# MaquetaConejos_2.net
KiCad netlist of a schematic drawn in EAGLE
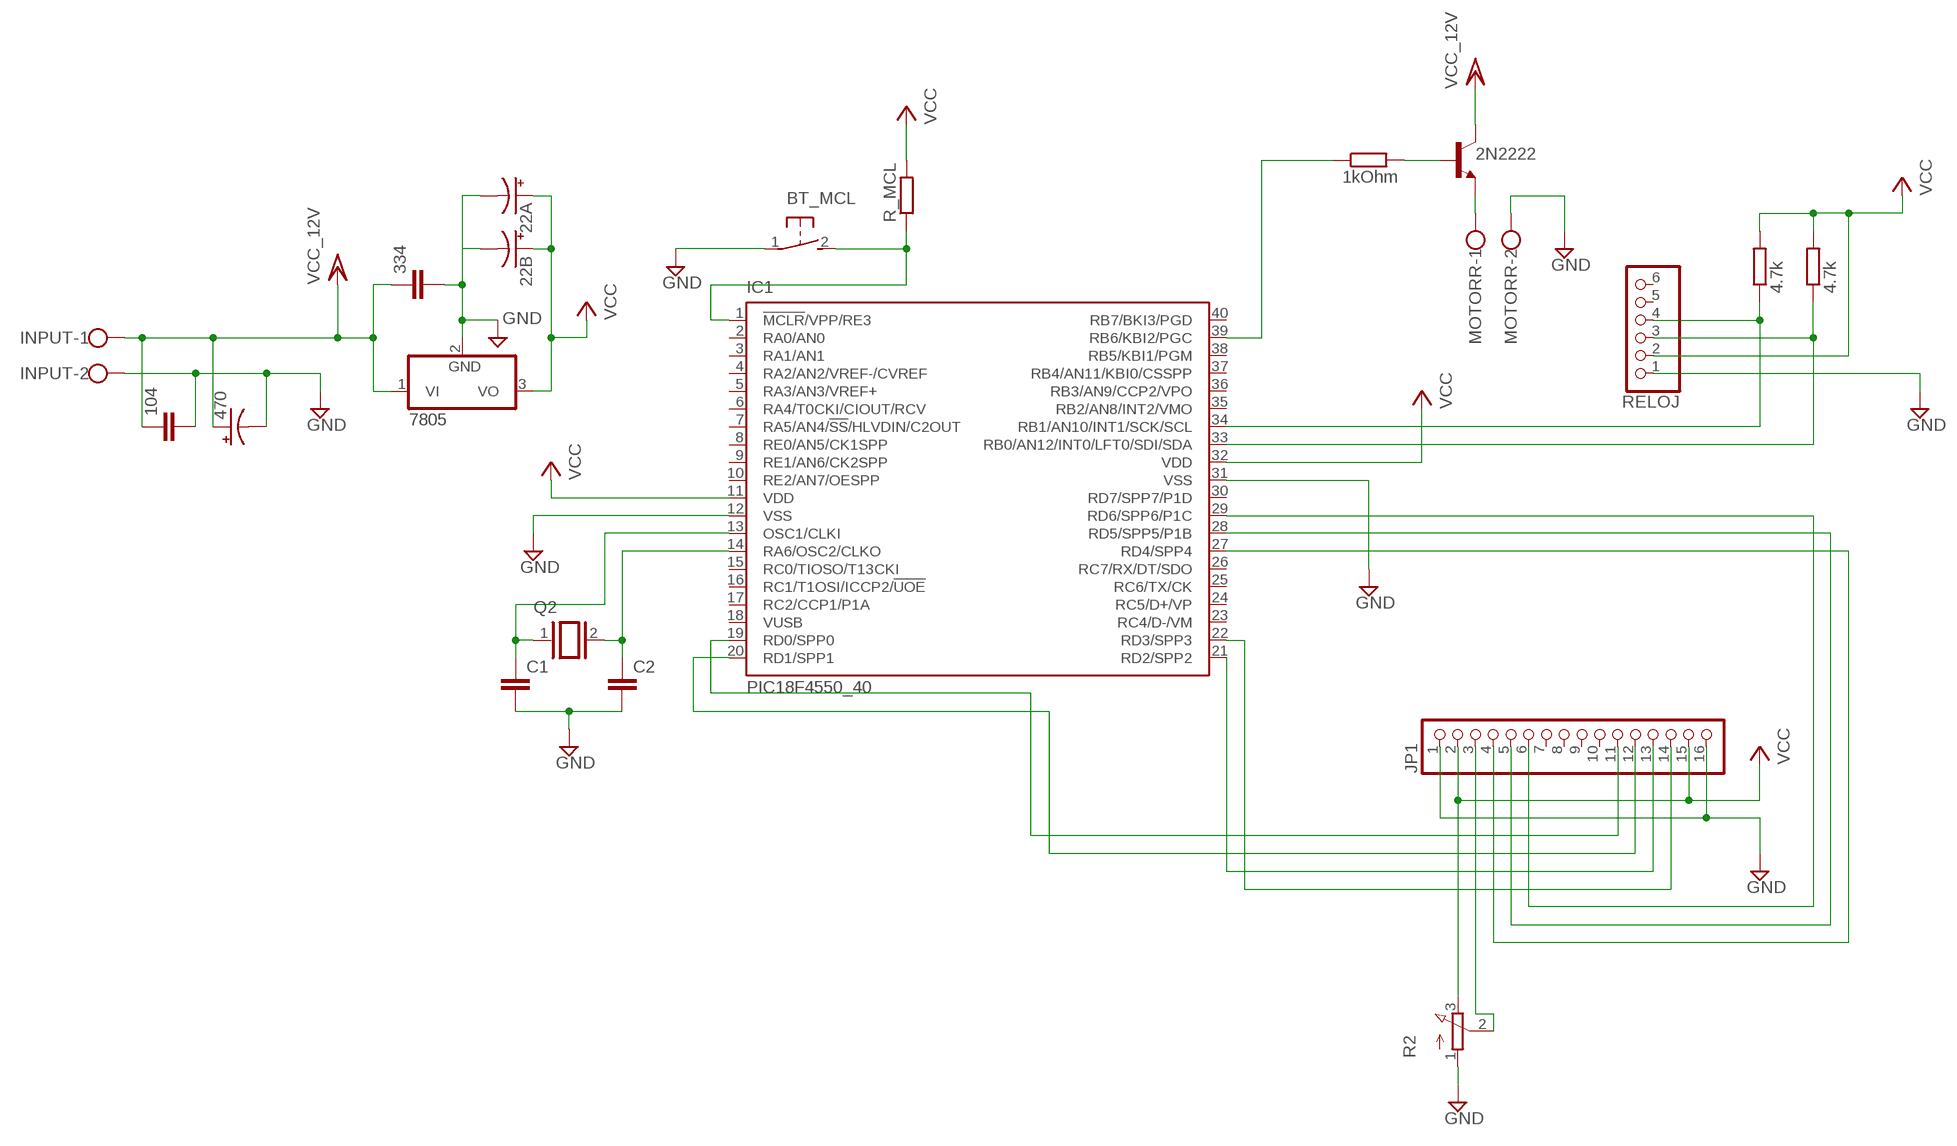
[diagram p0: schematic, sheet 1]

(export (version "E")
  (design (tool "Eeschema 10.0.6"))
  (components
    (comp (ref "22A")
      (value "CPOL-USE1.8-4")
      (footprint "eagle-import:E1,8-4")
      (libsource (lib "eagle-import") (part "CPOL-USE1.8-4"))
    )
    (comp (ref "22B")
      (value "CPOL-USE1.8-4")
      (footprint "eagle-import:E1,8-4")
      (libsource (lib "eagle-import") (part "CPOL-USE1.8-4"))
    )
    (comp (ref "104")
      (value "C-EU050-025X075")
      (footprint "eagle-import:C050-025X075")
      (libsource (lib "eagle-import") (part "rcl_334_C-EU050-025X075"))
    )
    (comp (ref "334")
      (value "C-EU050-025X075")
      (footprint "eagle-import:C050-025X075")
      (libsource (lib "eagle-import") (part "rcl_334_C-EU050-025X075"))
    )
    (comp (ref "470")
      (value "CPOL-USE5-10.5")
      (footprint "eagle-import:E5-10,5")
      (libsource (lib "eagle-import") (part "CPOL-USE5-10.5"))
    )
    (comp (ref "BT_MCL")
      (value "DTS-3")
      (footprint "eagle-import:DTS-3")
      (libsource (lib "eagle-import") (part "DTS-3"))
    )
    (comp (ref "C1")
      (value "C-EU025-024X044")
      (footprint "eagle-import:C025-024X044")
      (libsource (lib "eagle-import") (part "C-EU025-024X044"))
    )
    (comp (ref "C2")
      (value "C-EU025-024X044")
      (footprint "eagle-import:C025-024X044")
      (libsource (lib "eagle-import") (part "C-EU025-024X044"))
    )
    (comp (ref "IC1")
      (value "PIC18F4550_40")
      (footprint "eagle-import:DIL40")
      (fields (field (name "MF") "MICROCHIP") (field (name "MPN") "PIC18F4550-I/P"))
      (libsource (lib "eagle-import") (part "PIC18F4_40550"))
    )
    (comp (ref "IC3")
      (value "7805")
      (footprint "eagle-import:TO220V")
      (libsource (lib "eagle-import") (part "78TV05"))
    )
    (comp (ref "INPUT")
      (value "W237-102")
      (footprint "eagle-import:W237-102")
      (fields (field (name "MPN") "237-102"))
      (libsource (lib "eagle-import") (part "W237-102"))
    )
    (comp (ref "JP1")
      (value "PINHD-1X16")
      (footprint "eagle-import:1X16")
      (libsource (lib "eagle-import") (part "PINHD-1X16"))
    )
    (comp (ref "MOTORR")
      (value "W237-102")
      (footprint "eagle-import:W237-102")
      (fields (field (name "MPN") "237-102"))
      (libsource (lib "eagle-import") (part "con-wago-500_195_W237-102"))
    )
    (comp (ref "Q2")
      (value "XTAL/S")
      (footprint "eagle-import:QS")
      (libsource (lib "eagle-import") (part "XTAL/S"))
    )
    (comp (ref "R1")
      (value "4.7k")
      (footprint "eagle-import:0204_7")
      (libsource (lib "eagle-import") (part "rcl_334_R-EU_0204/7"))
    )
    (comp (ref "R2")
      (value "3RP/1610N")
      (footprint "eagle-import:3RP_1610N")
      (libsource (lib "eagle-import") (part "3RP/1610N"))
    )
    (comp (ref "R3")
      (value "1kOhm")
      (footprint "eagle-import:0204_7")
      (libsource (lib "eagle-import") (part "rcl_334_R-EU_0204/7"))
    )
    (comp (ref "R4")
      (value "4.7k")
      (footprint "eagle-import:0204_7")
      (libsource (lib "eagle-import") (part "rcl_334_R-EU_0204/7"))
    )
    (comp (ref "RELOJ")
      (value "PINHD-1X6")
      (footprint "eagle-import:1X06")
      (libsource (lib "eagle-import") (part "PINHD-1X6"))
    )
    (comp (ref "R_MCL")
      (value "R-EU_0204/7")
      (footprint "eagle-import:0204_7")
      (libsource (lib "eagle-import") (part "R-EU_0204/7"))
    )
    (comp (ref "T1")
      (value "2N2222")
      (footprint "eagle-import:TO92-EBC-OVAL")
      (libsource (lib "eagle-import") (part "2N2222"))
    )
  )
  (nets
    (net (code "1") (name "GND") (class "Default")
      (node (ref "104") (pin "2") (pinfunction "2_2") (pintype "passive"))
      (node (ref "22A") (pin "-") (pinfunction "-_-") (pintype "passive"))
      (node (ref "22B") (pin "-") (pinfunction "-_-") (pintype "passive"))
      (node (ref "334") (pin "2") (pinfunction "2_2") (pintype "passive"))
      (node (ref "470") (pin "-") (pinfunction "-_-") (pintype "passive"))
      (node (ref "BT_MCL") (pin "1") (pinfunction "1_1") (pintype "passive"))
      (node (ref "C1") (pin "2") (pinfunction "2_2") (pintype "passive"))
      (node (ref "C2") (pin "2") (pinfunction "2_2") (pintype "passive"))
      (node (ref "IC1") (pin "12") (pinfunction "VSS_12") (pintype "power_in"))
      (node (ref "IC1") (pin "31") (pinfunction "VSS_31") (pintype "power_in"))
      (node (ref "IC3") (pin "2") (pinfunction "GND_2") (pintype "passive"))
      (node (ref "INPUT") (pin "2") (pinfunction "KL_2") (pintype "passive"))
      (node (ref "JP1") (pin "1") (pinfunction "1_1") (pintype "passive"))
      (node (ref "JP1") (pin "16") (pinfunction "16_16") (pintype "passive"))
      (node (ref "MOTORR") (pin "2") (pinfunction "KL_2") (pintype "passive"))
      (node (ref "R2") (pin "1") (pinfunction "A_1") (pintype "passive"))
      (node (ref "RELOJ") (pin "1") (pinfunction "1_1") (pintype "passive"))
    )
    (net (code "2") (name "Net-(IC1-OSC1{slash}CLKI)") (class "Default")
      (node (ref "C1") (pin "1") (pinfunction "1_1") (pintype "passive"))
      (node (ref "IC1") (pin "13") (pinfunction "OSC1/CLKI_13") (pintype "input"))
      (node (ref "Q2") (pin "1") (pinfunction "1_1") (pintype "passive"))
    )
    (net (code "3") (name "Net-(IC1-RA6{slash}OSC2{slash}CLKO)") (class "Default")
      (node (ref "C2") (pin "1") (pinfunction "1_1") (pintype "passive"))
      (node (ref "IC1") (pin "14") (pinfunction "RA6/OSC2/CLKO_14") (pintype "output"))
      (node (ref "Q2") (pin "2") (pinfunction "2_2") (pintype "passive"))
    )
    (net (code "4") (name "Net-(IC1-RB0{slash}AN12{slash}INT0{slash}LFT0{slash}SDI{slash}SDA)") (class "Default")
      (node (ref "IC1") (pin "33") (pinfunction "RB0/AN12/INT0/LFT0/SDI/SDA_33") (pintype "bidirectional"))
      (node (ref "R1") (pin "1") (pinfunction "1_1") (pintype "passive"))
      (node (ref "RELOJ") (pin "3") (pinfunction "3_3") (pintype "passive"))
    )
    (net (code "5") (name "Net-(IC1-RB1{slash}AN10{slash}INT1{slash}SCK{slash}SCL)") (class "Default")
      (node (ref "IC1") (pin "34") (pinfunction "RB1/AN10/INT1/SCK/SCL_34") (pintype "bidirectional"))
      (node (ref "R4") (pin "1") (pinfunction "1_1") (pintype "passive"))
      (node (ref "RELOJ") (pin "4") (pinfunction "4_4") (pintype "passive"))
    )
    (net (code "6") (name "Net-(IC1-RB6{slash}KBI2{slash}PGC)") (class "Default")
      (node (ref "IC1") (pin "39") (pinfunction "RB6/KBI2/PGC_39") (pintype "bidirectional"))
      (node (ref "R3") (pin "1") (pinfunction "1_1") (pintype "passive"))
    )
    (net (code "7") (name "Net-(IC1-RD0{slash}SPP0)") (class "Default")
      (node (ref "IC1") (pin "19") (pinfunction "RD0/SPP0_19") (pintype "bidirectional"))
      (node (ref "JP1") (pin "11") (pinfunction "11_11") (pintype "passive"))
    )
    (net (code "8") (name "Net-(IC1-RD1{slash}SPP1)") (class "Default")
      (node (ref "IC1") (pin "20") (pinfunction "RD1/SPP1_20") (pintype "bidirectional"))
      (node (ref "JP1") (pin "12") (pinfunction "12_12") (pintype "passive"))
    )
    (net (code "9") (name "Net-(IC1-RD2{slash}SPP2)") (class "Default")
      (node (ref "IC1") (pin "21") (pinfunction "RD2/SPP2_21") (pintype "bidirectional"))
      (node (ref "JP1") (pin "13") (pinfunction "13_13") (pintype "passive"))
    )
    (net (code "10") (name "Net-(IC1-RD3{slash}SPP3)") (class "Default")
      (node (ref "IC1") (pin "22") (pinfunction "RD3/SPP3_22") (pintype "bidirectional"))
      (node (ref "JP1") (pin "14") (pinfunction "14_14") (pintype "passive"))
    )
    (net (code "11") (name "Net-(IC1-RD4{slash}SPP4)") (class "Default")
      (node (ref "IC1") (pin "27") (pinfunction "RD4/SPP4_27") (pintype "bidirectional"))
      (node (ref "JP1") (pin "4") (pinfunction "4_4") (pintype "passive"))
    )
    (net (code "12") (name "Net-(IC1-RD5{slash}SPP5{slash}P1B)") (class "Default")
      (node (ref "IC1") (pin "28") (pinfunction "RD5/SPP5/P1B_28") (pintype "bidirectional"))
      (node (ref "JP1") (pin "5") (pinfunction "5_5") (pintype "passive"))
    )
    (net (code "13") (name "Net-(IC1-RD6{slash}SPP6{slash}P1C)") (class "Default")
      (node (ref "IC1") (pin "29") (pinfunction "RD6/SPP6/P1C_29") (pintype "bidirectional"))
      (node (ref "JP1") (pin "6") (pinfunction "6_6") (pintype "passive"))
    )
    (net (code "14") (name "Net-(IC1-~{MCLR}{slash}VPP{slash}RE3)") (class "Default")
      (node (ref "BT_MCL") (pin "2") (pinfunction "2_2") (pintype "passive"))
      (node (ref "IC1") (pin "1") (pinfunction "~{MCLR}/VPP/RE3_1") (pintype "input"))
      (node (ref "R_MCL") (pin "1") (pinfunction "1_1") (pintype "passive"))
    )
    (net (code "15") (name "Net-(MOTORRA-KL)") (class "Default")
      (node (ref "MOTORR") (pin "1") (pinfunction "KL_1") (pintype "passive"))
      (node (ref "T1") (pin "E") (pinfunction "E_E") (pintype "passive"))
    )
    (net (code "16") (name "Net-(R2-S)") (class "Default")
      (node (ref "JP1") (pin "3") (pinfunction "3_3") (pintype "passive"))
      (node (ref "R2") (pin "2") (pinfunction "S_2") (pintype "passive"))
    )
    (net (code "17") (name "Net-(R3-Pad2)") (class "Default")
      (node (ref "R3") (pin "2") (pinfunction "2_2") (pintype "passive"))
      (node (ref "T1") (pin "B") (pinfunction "B_B") (pintype "passive"))
    )
    (net (code "18") (name "VCC") (class "Default")
      (node (ref "22A") (pin "+") (pinfunction "+_+") (pintype "passive"))
      (node (ref "22B") (pin "+") (pinfunction "+_+") (pintype "passive"))
      (node (ref "IC1") (pin "11") (pinfunction "VDD_11") (pintype "power_in"))
      (node (ref "IC1") (pin "32") (pinfunction "VDD_32") (pintype "power_in"))
      (node (ref "IC3") (pin "3") (pinfunction "VO_3") (pintype "passive"))
      (node (ref "JP1") (pin "15") (pinfunction "15_15") (pintype "passive"))
      (node (ref "JP1") (pin "2") (pinfunction "2_2") (pintype "passive"))
      (node (ref "R1") (pin "2") (pinfunction "2_2") (pintype "passive"))
      (node (ref "R2") (pin "3") (pinfunction "E_3") (pintype "passive"))
      (node (ref "R4") (pin "2") (pinfunction "2_2") (pintype "passive"))
      (node (ref "RELOJ") (pin "2") (pinfunction "2_2") (pintype "passive"))
      (node (ref "R_MCL") (pin "2") (pinfunction "2_2") (pintype "passive"))
    )
    (net (code "19") (name "VCC_12V") (class "Default")
      (node (ref "104") (pin "1") (pinfunction "1_1") (pintype "passive"))
      (node (ref "334") (pin "1") (pinfunction "1_1") (pintype "passive"))
      (node (ref "470") (pin "+") (pinfunction "+_+") (pintype "passive"))
      (node (ref "IC3") (pin "1") (pinfunction "VI_1") (pintype "input"))
      (node (ref "INPUT") (pin "1") (pinfunction "KL_1") (pintype "passive"))
      (node (ref "T1") (pin "C") (pinfunction "C_C") (pintype "passive"))
    )
    (net (code "20") (name "unconnected-(IC1-RA0{slash}AN0-Pad2)") (class "Default")
      (node (ref "IC1") (pin "2") (pinfunction "RA0/AN0_2") (pintype "bidirectional"))
    )
    (net (code "21") (name "unconnected-(IC1-RA1{slash}AN1-Pad3)") (class "Default")
      (node (ref "IC1") (pin "3") (pinfunction "RA1/AN1_3") (pintype "bidirectional"))
    )
    (net (code "22") (name "unconnected-(IC1-RA2{slash}AN2{slash}VREF-{slash}CVREF-Pad4)") (class "Default")
      (node (ref "IC1") (pin "4") (pinfunction "RA2/AN2/VREF-/CVREF_4") (pintype "bidirectional"))
    )
    (net (code "23") (name "unconnected-(IC1-RA3{slash}AN3{slash}VREF+-Pad5)") (class "Default")
      (node (ref "IC1") (pin "5") (pinfunction "RA3/AN3/VREF+_5") (pintype "bidirectional"))
    )
    (net (code "24") (name "unconnected-(IC1-RA4{slash}T0CKI{slash}CIOUT{slash}RCV-Pad6)") (class "Default")
      (node (ref "IC1") (pin "6") (pinfunction "RA4/T0CKI/CIOUT/RCV_6") (pintype "bidirectional"))
    )
    (net (code "25") (name "unconnected-(IC1-RA5{slash}AN4{slash}~{SS}{slash}HLVDIN{slash}C2OUT-Pad7)") (class "Default")
      (node (ref "IC1") (pin "7") (pinfunction "RA5/AN4/~{SS}/HLVDIN/C2OUT_7") (pintype "bidirectional"))
    )
    (net (code "26") (name "unconnected-(IC1-RB2{slash}AN8{slash}INT2{slash}VMO-Pad35)") (class "Default")
      (node (ref "IC1") (pin "35") (pinfunction "RB2/AN8/INT2/VMO_35") (pintype "bidirectional"))
    )
    (net (code "27") (name "unconnected-(IC1-RB3{slash}AN9{slash}CCP2{slash}VPO-Pad36)") (class "Default")
      (node (ref "IC1") (pin "36") (pinfunction "RB3/AN9/CCP2/VPO_36") (pintype "bidirectional"))
    )
    (net (code "28") (name "unconnected-(IC1-RB4{slash}AN11{slash}KBI0{slash}CSSPP-Pad37)") (class "Default")
      (node (ref "IC1") (pin "37") (pinfunction "RB4/AN11/KBI0/CSSPP_37") (pintype "bidirectional"))
    )
    (net (code "29") (name "unconnected-(IC1-RB5{slash}KBI1{slash}PGM-Pad38)") (class "Default")
      (node (ref "IC1") (pin "38") (pinfunction "RB5/KBI1/PGM_38") (pintype "bidirectional"))
    )
    (net (code "30") (name "unconnected-(IC1-RB7{slash}BKI3{slash}PGD-Pad40)") (class "Default")
      (node (ref "IC1") (pin "40") (pinfunction "RB7/BKI3/PGD_40") (pintype "bidirectional"))
    )
    (net (code "31") (name "unconnected-(IC1-RC0{slash}TIOSO{slash}T13CKI-Pad15)") (class "Default")
      (node (ref "IC1") (pin "15") (pinfunction "RC0/TIOSO/T13CKI_15") (pintype "bidirectional"))
    )
    (net (code "32") (name "unconnected-(IC1-RC1{slash}T1OSI{slash}ICCP2{slash}~{UOE}-Pad16)") (class "Default")
      (node (ref "IC1") (pin "16") (pinfunction "RC1/T1OSI/ICCP2/~{UOE}_16") (pintype "bidirectional"))
    )
    (net (code "33") (name "unconnected-(IC1-RC2{slash}CCP1{slash}P1A-Pad17)") (class "Default")
      (node (ref "IC1") (pin "17") (pinfunction "RC2/CCP1/P1A_17") (pintype "bidirectional"))
    )
    (net (code "34") (name "unconnected-(IC1-RC4{slash}D-{slash}VM-Pad23)") (class "Default")
      (node (ref "IC1") (pin "23") (pinfunction "RC4/D-/VM_23") (pintype "bidirectional"))
    )
    (net (code "35") (name "unconnected-(IC1-RC5{slash}D+{slash}VP-Pad24)") (class "Default")
      (node (ref "IC1") (pin "24") (pinfunction "RC5/D+/VP_24") (pintype "bidirectional"))
    )
    (net (code "36") (name "unconnected-(IC1-RC6{slash}TX{slash}CK-Pad25)") (class "Default")
      (node (ref "IC1") (pin "25") (pinfunction "RC6/TX/CK_25") (pintype "bidirectional"))
    )
    (net (code "37") (name "unconnected-(IC1-RC7{slash}RX{slash}DT{slash}SDO-Pad26)") (class "Default")
      (node (ref "IC1") (pin "26") (pinfunction "RC7/RX/DT/SDO_26") (pintype "bidirectional"))
    )
    (net (code "38") (name "unconnected-(IC1-RD7{slash}SPP7{slash}P1D-Pad30)") (class "Default")
      (node (ref "IC1") (pin "30") (pinfunction "RD7/SPP7/P1D_30") (pintype "bidirectional"))
    )
    (net (code "39") (name "unconnected-(IC1-RE0{slash}AN5{slash}CK1SPP-Pad8)") (class "Default")
      (node (ref "IC1") (pin "8") (pinfunction "RE0/AN5/CK1SPP_8") (pintype "bidirectional"))
    )
    (net (code "40") (name "unconnected-(IC1-RE1{slash}AN6{slash}CK2SPP-Pad9)") (class "Default")
      (node (ref "IC1") (pin "9") (pinfunction "RE1/AN6/CK2SPP_9") (pintype "bidirectional"))
    )
    (net (code "41") (name "unconnected-(IC1-RE2{slash}AN7{slash}OESPP-Pad10)") (class "Default")
      (node (ref "IC1") (pin "10") (pinfunction "RE2/AN7/OESPP_10") (pintype "bidirectional"))
    )
    (net (code "42") (name "unconnected-(IC1-VUSB-Pad18)") (class "Default")
      (node (ref "IC1") (pin "18") (pinfunction "VUSB_18") (pintype "bidirectional"))
    )
    (net (code "43") (name "unconnected-(JP1-Pad7)") (class "Default")
      (node (ref "JP1") (pin "7") (pinfunction "7_7") (pintype "passive"))
    )
    (net (code "44") (name "unconnected-(JP1-Pad8)") (class "Default")
      (node (ref "JP1") (pin "8") (pinfunction "8_8") (pintype "passive"))
    )
    (net (code "45") (name "unconnected-(JP1-Pad9)") (class "Default")
      (node (ref "JP1") (pin "9") (pinfunction "9_9") (pintype "passive"))
    )
    (net (code "46") (name "unconnected-(JP1-Pad10)") (class "Default")
      (node (ref "JP1") (pin "10") (pinfunction "10_10") (pintype "passive"))
    )
    (net (code "47") (name "unconnected-(RELOJ-Pad5)") (class "Default")
      (node (ref "RELOJ") (pin "5") (pinfunction "5_5") (pintype "passive"))
    )
    (net (code "48") (name "unconnected-(RELOJ-Pad6)") (class "Default")
      (node (ref "RELOJ") (pin "6") (pinfunction "6_6") (pintype "passive"))
    )
  )
)
